# Power_Supply_3.net
KiCad netlist of a schematic drawn in Altium Designer
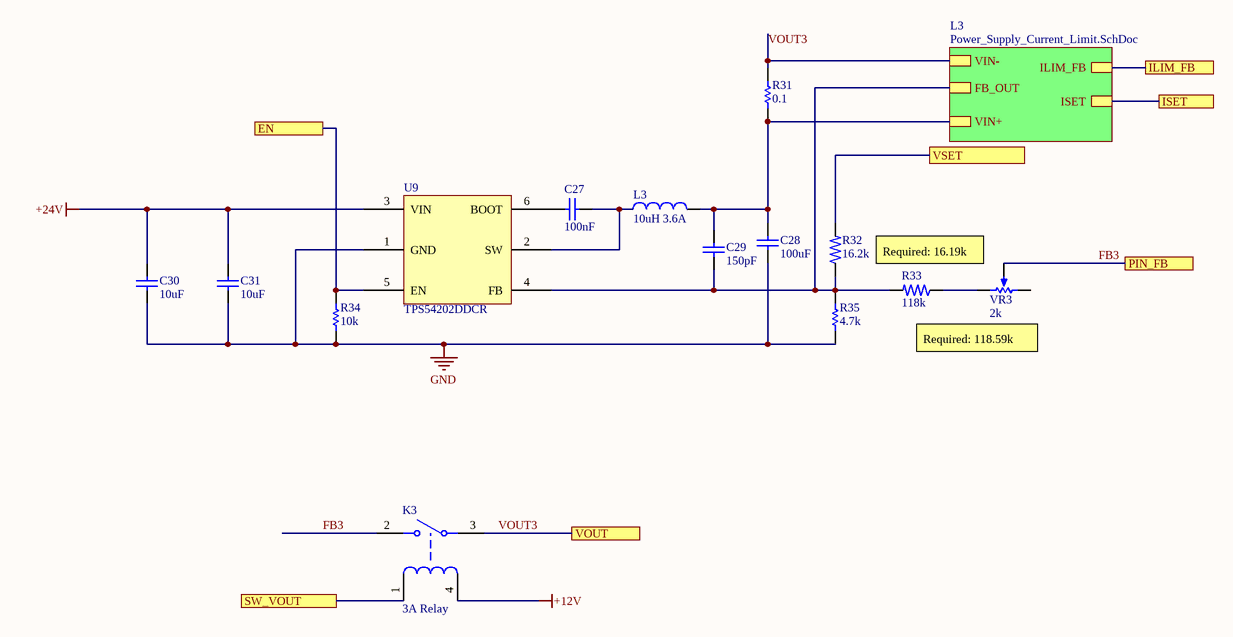
[diagram p0: Power_Supply_3.SchDoc]

(export (version "E")
  (design (tool "Eeschema 10.0.6"))
  (components
    (comp (ref "C27")
      (value "100nF")
      (footprint "CAPC1608X09N")
      (description "0603 10 nF 50 V ± 10% Tolerance X7R Surface Mount Multilayer Ceramic Capacitor")
      (fields
        (field (name "MANUFACTURE PART NUMBER") "CC0603KRX7R9BB104")
        (field (name "MANUFACTURER") "YAGEO")
      )
      (libsource (lib "POWER CARD") (part "CMP-2f55e5122ad9f092-5"))
    )
    (comp (ref "C28")
      (value "100uF")
      (footprint "PCB-qvt8zv9h5ffid452gs9x-1")
      (description "Footprint for Rubycon 50YXF100MFFC8X11.5")
      (fields
        (field (name "MANUFACTURE PART NUMBER") "50YXF100MFFC8X11.5")
        (field (name "MANUFACTURER") "Rubycon")
      )
      (libsource (lib "POWER CARD") (part "CMP-37c1fb270af2e806-1"))
    )
    (comp (ref "C29")
      (value "150pF")
      (footprint "C0805")
      (description "Cap Ceramic 0.1uF 50V X7R 10% SMD 0805 125C Embossed T/R")
      (fields
        (field (name "MANUFACTURE PART NUMBER") "CC0805JRNPO9BN151")
        (field (name "MANUFACTURER") "YAGEO")
      )
      (libsource (lib "POWER CARD") (part "CMP-135114-3"))
    )
    (comp (ref "C30")
      (value "10uF")
      (footprint "CAPC3216X127X50ML20T25")
      (description "CAP CER 0.1UF 100V 10% X7R 1206")
      (fields
        (field (name "MANUFACTURER") "Samsung Electro-Mechanics")
        (field (name "MANUFACTURE PART NUMBER") "CL31B106KBHNNNE")
      )
      (libsource (lib "POWER CARD") (part "CMP-126371-4"))
    )
    (comp (ref "C31")
      (value "10uF")
      (footprint "CAPC3216X127X50ML20T25")
      (description "CAP CER 0.1UF 100V 10% X7R 1206")
      (fields
        (field (name "MANUFACTURE PART NUMBER") "CL31B106KBHNNNE")
        (field (name "MANUFACTURER") "Samsung Electro-Mechanics")
      )
      (libsource (lib "POWER CARD") (part "CMP-126371-4"))
    )
    (comp (ref "K3")
      (value "3A Relay")
      (footprint "PCB-ei6nokn2irsc2a7yt94x-1")
      (description "Power Relay 12VDC 3DC/5AAC SPST-NO( (20.5mm 7.2mm 15.3mm)) THT")
      (fields
        (field (name "MANUFACTURER") "Omron Electronics")
        (field (name "MANUFACTURE PART NUMBER") "G5NB-1A-E-DC12")
      )
      (libsource (lib "POWER CARD") (part "CMP-edc624afa9603201-3"))
    )
    (comp (ref "L3")
      (value "10uH 3.6A")
      (footprint "PCB-aqghgth2fl3irtnr7nhi-1")
      (description "Inductor Power Shielded Wirewound 10uH 20% 100KHz Metal 4.2A 86.35mOhm DCR Automotive T/R")
      (fields (field (name "MANUFACTURE PART NUMBER") "SPM6530T-100M-HZ") (field (name "MANUFACTURER") "TDK"))
      (libsource (lib "POWER CARD") (part "CMP-8deb4183ed4a522c-1"))
    )
    (comp (ref "R31")
      (value "0.1")
      (footprint "RESC3116X07M")
      (description "Res Thick Film 3.2 x 1.6 mm 10K Ohm 1% 0.25W(1/4W) 100ppm/ C Molded SMD Paper T/R")
      (fields
        (field (name "MANUFACTURE PART NUMBER") "1206W4F100LT5E")
        (field (name "MANUFACTURER") "UNI-ROYAL(Uniroyal Elec)")
      )
      (libsource (lib "POWER CARD") (part "CMP-90ca5a8d69034f0d-5"))
    )
    (comp (ref "R32")
      (value "16.2k")
      (footprint "PCB-3elf45qdqizoabmczrxc-1")
      (description "Surface Mount Thick Film Resistor, RC Series, 1 kohm, 100 mW, - 1%, 50 V, 0603 [1608 Metric]")
      (fields
        (field (name "MANUFACTURER") "UNI-ROYAL(Uniroyal Elec)")
        (field (name "MANUFACTURE PART NUMBER") "0603WAF1622T5E")
      )
      (libsource (lib "POWER CARD") (part "CMP-1853278-23"))
    )
    (comp (ref "R33")
      (value "118k")
      (footprint "PCB-3elf45qdqizoabmczrxc-1")
      (description "Surface Mount Thick Film Resistor, RC Series, 1 kohm, 100 mW, - 1%, 50 V, 0603 [1608 Metric]")
      (fields
        (field (name "MANUFACTURER") "UNI-ROYAL(Uniroyal Elec)")
        (field (name "MANUFACTURE PART NUMBER") "0603WAF1183T5E")
      )
      (libsource (lib "POWER CARD") (part "CMP-1853278-23"))
    )
    (comp (ref "R34")
      (value "10k")
      (footprint "gen0603-2")
      (description "Surface Mount Thick Film Resistor, RC Series, 1 kohm, 100 mW, - 1%, 50 V, 0603 [1608 Metric]")
      (fields
        (field (name "MANUFACTURER") "YAGEO")
        (field (name "MANUFACTURE PART NUMBER") "RC0603FR-0710KL")
      )
      (libsource (lib "POWER CARD") (part "CMP-1853278-27"))
    )
    (comp (ref "R35")
      (value "4.7k")
      (footprint "gen0603-2")
      (description "Surface Mount Thick Film Resistor, RC Series, 1 kohm, 100 mW, - 1%, 50 V, 0603 [1608 Metric]")
      (fields
        (field (name "MANUFACTURE PART NUMBER") "RC0603FR-074K7L")
        (field (name "MANUFACTURER") "YAGEO")
      )
      (libsource (lib "POWER CARD") (part "CMP-1853278-27"))
    )
    (comp (ref "U9")
      (value "TPS54202DDCR")
      (footprint "PCB-3e3nvufahczdahdcyxrk-1")
      (description "Conv DC-DC 4.5V to 28V Synchronous Step Down Single-Out -0.1V to 28V 2A 6-Pin TSOT-23 T/R")
      (fields (field (name "MANUFACTURER") "Texas Instruments"))
      (libsource (lib "POWER CARD") (part "CMP-793bb472c98da6fc-1"))
    )
    (comp (ref "VR3")
      (value "2k")
      (footprint "PCB-5abvnr99iwiiosfurk6j-1")
      (description "Res Cermet Trimmer 2K Ohm 10% 1/2W 25(Elec)Turn 2.19mm (9.53 X 4.83 X 11.55mm) Pin Thru-Hole Tube")
      (fields
        (field (name "MANUFACTURE PART NUMBER") "3296W-1-202")
        (field (name "MANUFACTURER") "BOCHEN(Chengdu Guosheng Tech)")
      )
      (libsource (lib "POWER CARD") (part "CMP-a8df61d7bf077718-3"))
    )
  )
  (nets
    (net (code "1") (name "+12V") (class "Default")
      (node (ref "K3") (pin "4") (pinfunction "4_4") (pintype "passive"))
    )
    (net (code "2") (name "+24V") (class "Default")
      (node (ref "C30") (pin "2") (pinfunction "2_2") (pintype "passive"))
      (node (ref "C31") (pin "2") (pinfunction "2_2") (pintype "passive"))
      (node (ref "U9") (pin "3") (pinfunction "VIN_3") (pintype "passive"))
    )
    (net (code "3") (name "/EN") (class "Default")
      (node (ref "R34") (pin "1") (pinfunction "1_1") (pintype "passive"))
      (node (ref "U9") (pin "5") (pinfunction "EN_5") (pintype "passive"))
    )
    (net (code "4") (name "/FB3") (class "Default")
      (node (ref "K3") (pin "2") (pinfunction "2_2") (pintype "passive"))
      (node (ref "VR3") (pin "2") (pinfunction "WIPER_2") (pintype "passive"))
    )
    (net (code "5") (name "/FB_OUT") (class "Default")
      (node (ref "C29") (pin "1") (pinfunction "1_1") (pintype "passive"))
      (node (ref "R32") (pin "1") (pinfunction "1_1") (pintype "passive"))
      (node (ref "R33") (pin "2") (pinfunction "2_2") (pintype "passive"))
      (node (ref "R35") (pin "2") (pinfunction "2_2") (pintype "passive"))
      (node (ref "U9") (pin "4") (pinfunction "FB_4") (pintype "passive"))
    )
    (net (code "8") (name "/SW_VOUT") (class "Default")
      (node (ref "K3") (pin "1") (pinfunction "1_1") (pintype "passive"))
    )
    (net (code "9") (name "/VIN+") (class "Default")
      (node (ref "C28") (pin "2") (pinfunction "2_2") (pintype "passive"))
      (node (ref "C29") (pin "2") (pinfunction "2_2") (pintype "passive"))
      (node (ref "L3") (pin "2") (pinfunction "2_2") (pintype "passive"))
      (node (ref "R31") (pin "2") (pinfunction "2_2") (pintype "passive"))
    )
    (net (code "10") (name "/VOUT3") (class "Default")
      (node (ref "K3") (pin "3") (pinfunction "3_3") (pintype "passive"))
      (node (ref "R31") (pin "1") (pinfunction "1_1") (pintype "passive"))
    )
    (net (code "11") (name "/VSET") (class "Default")
      (node (ref "R32") (pin "2") (pinfunction "2_2") (pintype "passive"))
    )
    (net (code "12") (name "GND") (class "Default")
      (node (ref "C28") (pin "1") (pinfunction "1_1") (pintype "passive"))
      (node (ref "C30") (pin "1") (pinfunction "1_1") (pintype "passive"))
      (node (ref "C31") (pin "1") (pinfunction "1_1") (pintype "passive"))
      (node (ref "R34") (pin "2") (pinfunction "2_2") (pintype "passive"))
      (node (ref "R35") (pin "1") (pinfunction "1_1") (pintype "passive"))
      (node (ref "U9") (pin "1") (pinfunction "GND_1") (pintype "passive"))
    )
    (net (code "13") (name "Net-(U9-BOOT)") (class "Default")
      (node (ref "C27") (pin "2") (pinfunction "2_2") (pintype "passive"))
      (node (ref "U9") (pin "6") (pinfunction "BOOT_6") (pintype "passive"))
    )
    (net (code "14") (name "Net-(U9-SW)") (class "Default")
      (node (ref "C27") (pin "1") (pinfunction "1_1") (pintype "passive"))
      (node (ref "L3") (pin "1") (pinfunction "1_1") (pintype "passive"))
      (node (ref "U9") (pin "2") (pinfunction "SW_2") (pintype "passive"))
    )
    (net (code "15") (name "Net-(VR3-CCW)") (class "Default")
      (node (ref "R33") (pin "1") (pinfunction "1_1") (pintype "passive"))
      (node (ref "VR3") (pin "1") (pinfunction "CCW_1") (pintype "passive"))
    )
    (net (code "16") (name "unconnected-(VR3-CW-Pad3)") (class "Default")
      (node (ref "VR3") (pin "3") (pinfunction "CW_3") (pintype "passive"))
    )
  )
)
